# FPGA_Bank_0_CFG.net
KiCad netlist of a schematic drawn in Altium Designer
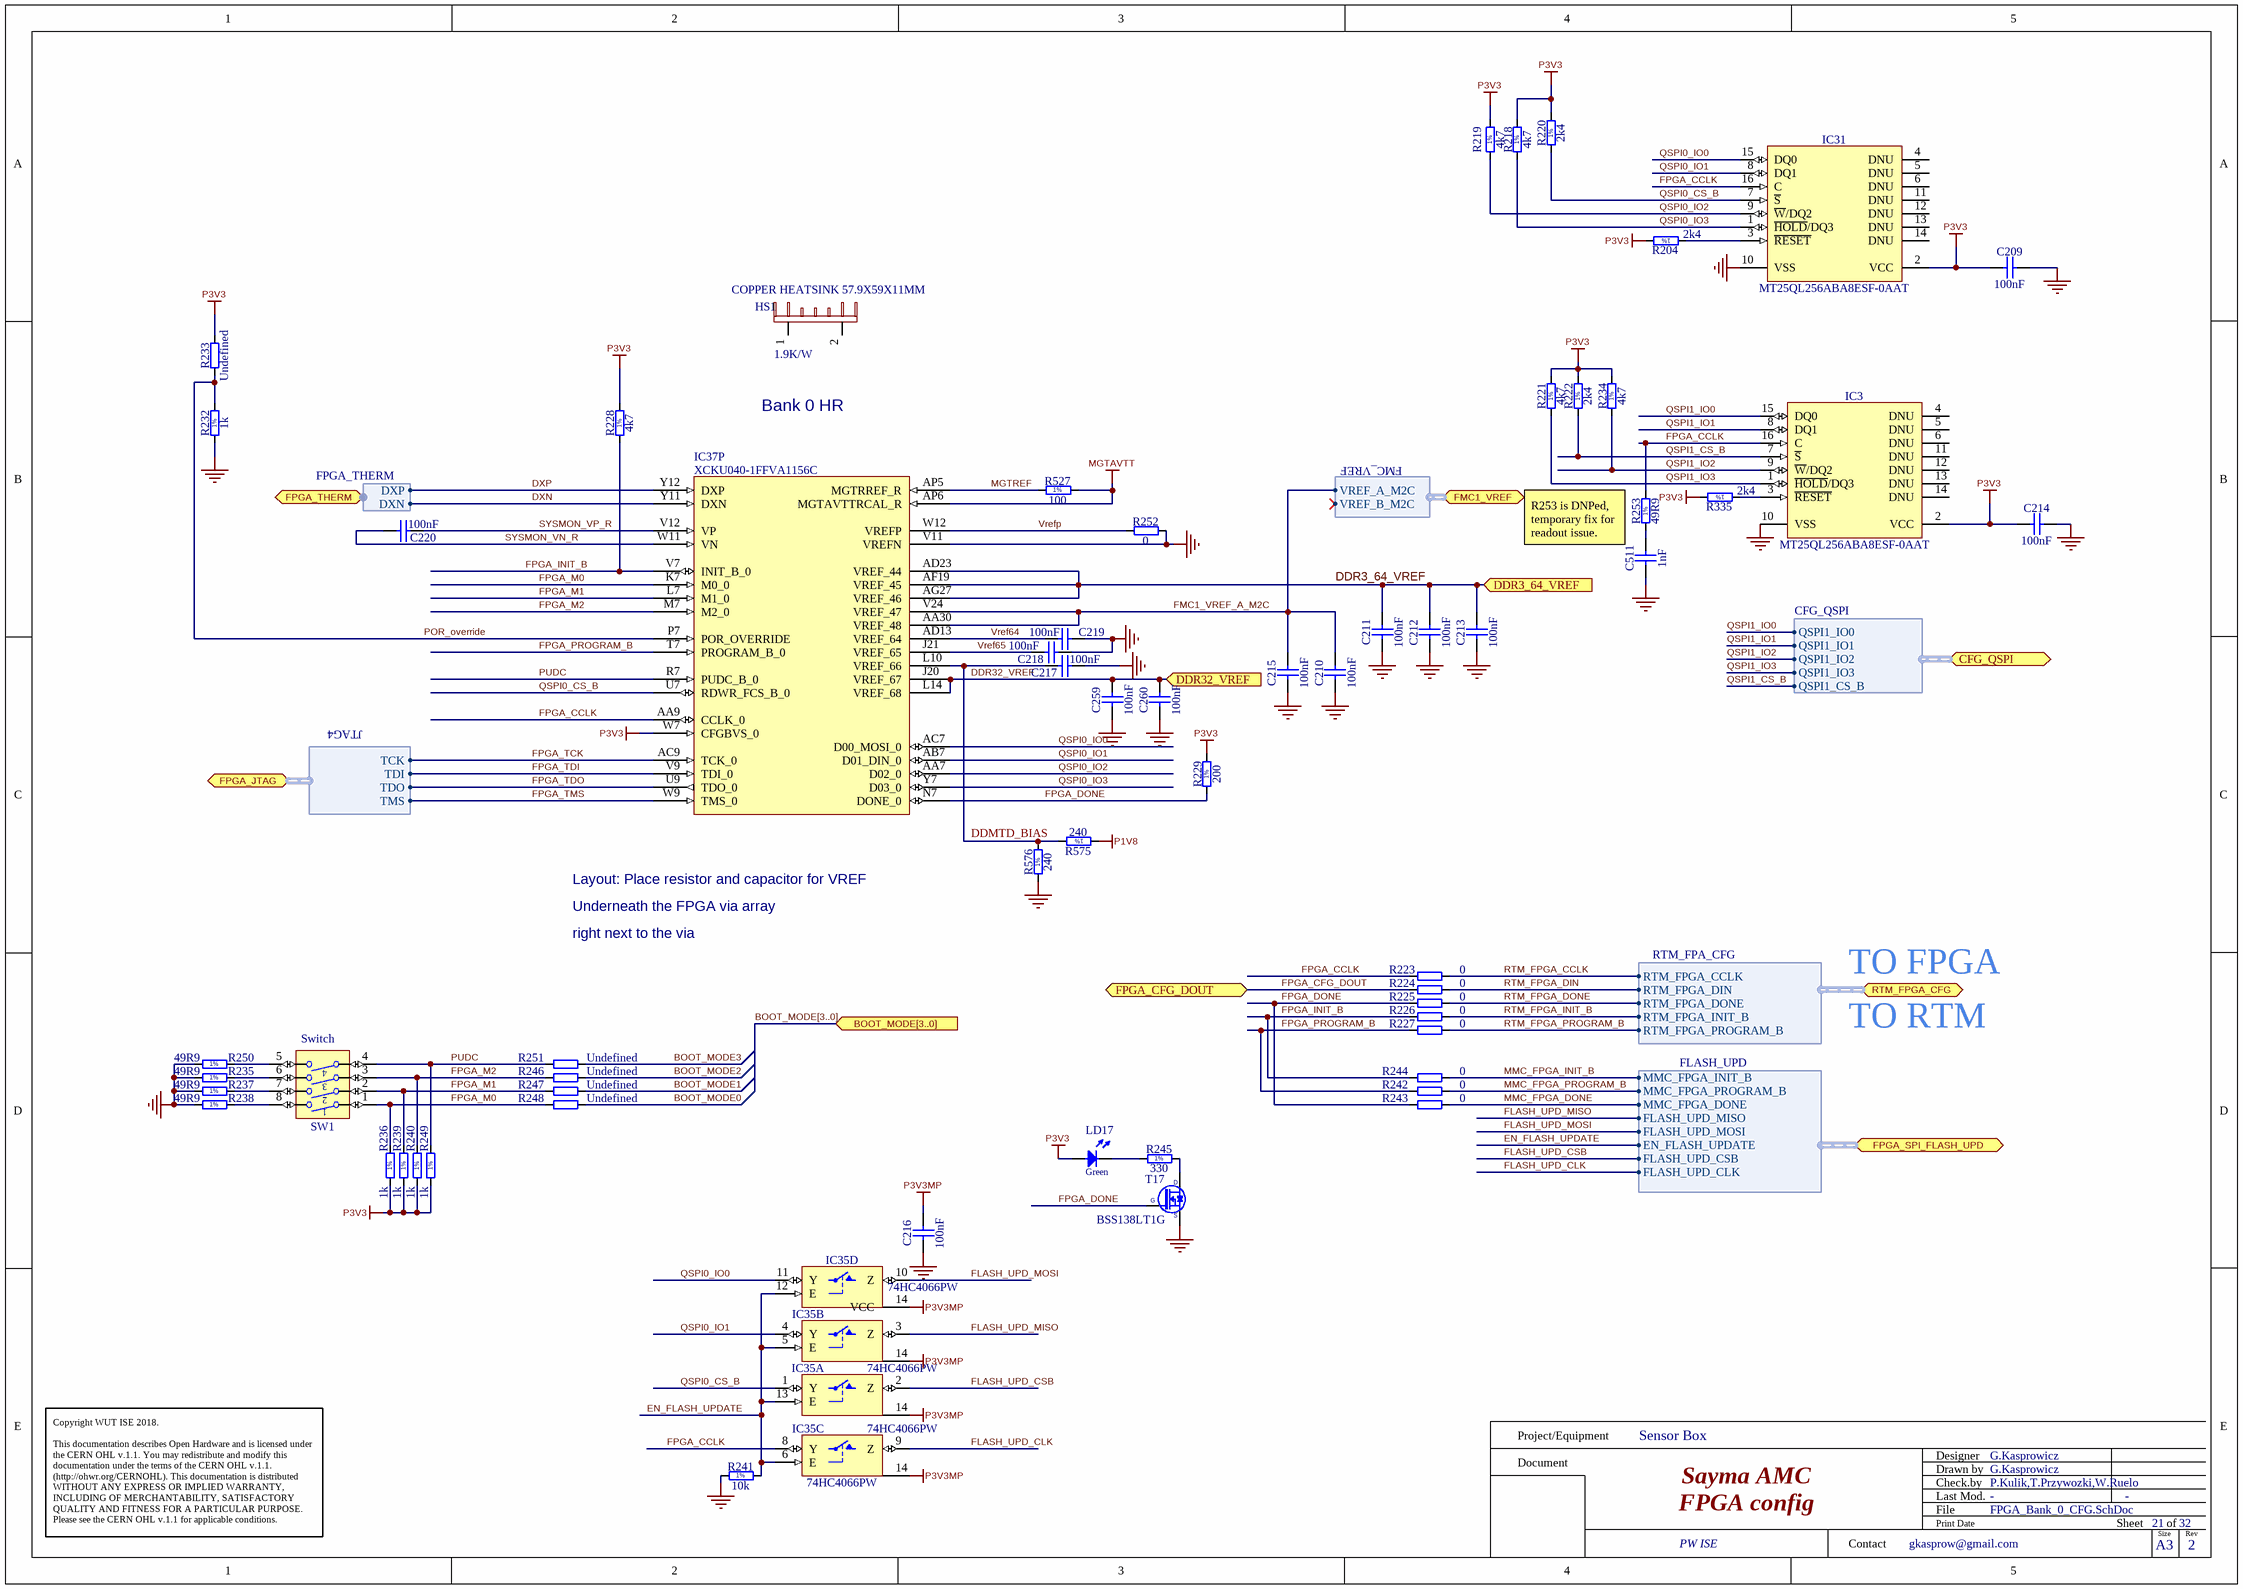
[diagram p0: FPGA_Bank_0_CFG.SchDoc]

(export (version "E")
  (design (tool "Eeschema 10.0.6"))
  (components
    (comp (ref "C209")
      (value "100nF")
      (footprint "CAPC0603X33N")
      (description "Non-polarised capacitor")
      (fields
        (field (name "MANUFACTURER PART NUMBER") "CC0201_100NF_6.3V_10%_X5R")
        (field (name "MANUFACTURER") "GENERIC")
        (field (name "AUTHOR") "CERN DEM JLC")
      )
      (libsource (lib "Capacitors") (part "Capacitor - non polarized"))
    )
    (comp (ref "C210")
      (value "100nF")
      (footprint "CAPC0603X33N")
      (description "Non-polarised capacitor")
      (fields
        (field (name "MANUFACTURER PART NUMBER") "CC0201_100NF_6.3V_10%_X5R")
        (field (name "MANUFACTURER") "GENERIC")
        (field (name "AUTHOR") "CERN DEM JLC")
      )
      (libsource (lib "Capacitors") (part "Capacitor - non polarized"))
    )
    (comp (ref "C211")
      (value "100nF")
      (footprint "CAPC0603X33N")
      (description "Non-polarised capacitor")
      (fields
        (field (name "MANUFACTURER PART NUMBER") "CC0201_100NF_6.3V_10%_X5R")
        (field (name "MANUFACTURER") "GENERIC")
        (field (name "AUTHOR") "CERN DEM JLC")
      )
      (libsource (lib "Capacitors") (part "Capacitor - non polarized"))
    )
    (comp (ref "C212")
      (value "100nF")
      (footprint "CAPC0603X33N")
      (description "Non-polarised capacitor")
      (fields
        (field (name "MANUFACTURER PART NUMBER") "CC0201_100NF_6.3V_10%_X5R")
        (field (name "MANUFACTURER") "GENERIC")
        (field (name "AUTHOR") "CERN DEM JLC")
      )
      (libsource (lib "Capacitors") (part "Capacitor - non polarized"))
    )
    (comp (ref "C213")
      (value "100nF")
      (footprint "CAPC0603X33N")
      (description "Non-polarised capacitor")
      (fields
        (field (name "MANUFACTURER PART NUMBER") "CC0201_100NF_6.3V_10%_X5R")
        (field (name "MANUFACTURER") "GENERIC")
        (field (name "AUTHOR") "CERN DEM JLC")
      )
      (libsource (lib "Capacitors") (part "Capacitor - non polarized"))
    )
    (comp (ref "C214")
      (value "100nF")
      (footprint "CAPC0603X33N")
      (description "Non-polarised capacitor")
      (fields
        (field (name "MANUFACTURER PART NUMBER") "CC0201_100NF_6.3V_10%_X5R")
        (field (name "MANUFACTURER") "GENERIC")
        (field (name "AUTHOR") "CERN DEM JLC")
      )
      (libsource (lib "Capacitors") (part "Capacitor - non polarized"))
    )
    (comp (ref "C215")
      (value "100nF")
      (footprint "CAPC0603X33N")
      (description "Non-polarised capacitor")
      (fields
        (field (name "MANUFACTURER PART NUMBER") "CC0201_100NF_6.3V_10%_X5R")
        (field (name "MANUFACTURER") "GENERIC")
        (field (name "AUTHOR") "CERN DEM JLC")
      )
      (libsource (lib "Capacitors") (part "Capacitor - non polarized"))
    )
    (comp (ref "C216")
      (value "100nF")
      (footprint "CAPC0603X33N")
      (description "Non-polarised capacitor")
      (fields
        (field (name "MANUFACTURER PART NUMBER") "CC0201_100NF_6.3V_10%_X5R")
        (field (name "MANUFACTURER") "GENERIC")
        (field (name "AUTHOR") "CERN DEM JLC")
      )
      (libsource (lib "Capacitors") (part "Capacitor - non polarized"))
    )
    (comp (ref "C217")
      (value "100nF")
      (footprint "CAPC0603X33N")
      (description "Non-polarised capacitor")
      (fields
        (field (name "MANUFACTURER PART NUMBER") "CC0201_100NF_6.3V_10%_X5R")
        (field (name "MANUFACTURER") "GENERIC")
        (field (name "AUTHOR") "CERN DEM JLC")
      )
      (libsource (lib "Capacitors") (part "Capacitor - non polarized"))
    )
    (comp (ref "C218")
      (value "100nF")
      (footprint "CAPC0603X33N")
      (description "Non-polarised capacitor")
      (fields
        (field (name "MANUFACTURER PART NUMBER") "CC0201_100NF_6.3V_10%_X5R")
        (field (name "MANUFACTURER") "GENERIC")
        (field (name "AUTHOR") "CERN DEM JLC")
      )
      (libsource (lib "Capacitors") (part "Capacitor - non polarized"))
    )
    (comp (ref "C219")
      (value "100nF")
      (footprint "CAPC0603X33N")
      (description "Non-polarised capacitor")
      (fields
        (field (name "MANUFACTURER PART NUMBER") "CC0201_100NF_6.3V_10%_X5R")
        (field (name "MANUFACTURER") "GENERIC")
        (field (name "AUTHOR") "CERN DEM JLC")
      )
      (libsource (lib "Capacitors") (part "Capacitor - non polarized"))
    )
    (comp (ref "C220")
      (value "100nF")
      (footprint "CAPC0603X33N")
      (description "Non-polarised capacitor")
      (fields
        (field (name "MANUFACTURER PART NUMBER") "CC0201_100NF_6.3V_10%_X5R")
        (field (name "MANUFACTURER") "GENERIC")
        (field (name "AUTHOR") "CERN DEM JLC")
      )
      (libsource (lib "Capacitors") (part "Capacitor - non polarized"))
    )
    (comp (ref "C259")
      (value "100nF")
      (footprint "CAPC0603X33N")
      (description "Non-polarised capacitor")
      (fields
        (field (name "MANUFACTURER PART NUMBER") "CC0201_100NF_6.3V_10%_X5R")
        (field (name "MANUFACTURER") "GENERIC")
        (field (name "AUTHOR") "CERN DEM JLC")
      )
      (libsource (lib "Capacitors") (part "Capacitor - non polarized"))
    )
    (comp (ref "C260")
      (value "100nF")
      (footprint "CAPC0603X33N")
      (description "Non-polarised capacitor")
      (fields
        (field (name "MANUFACTURER PART NUMBER") "CC0201_100NF_6.3V_10%_X5R")
        (field (name "MANUFACTURER") "GENERIC")
        (field (name "AUTHOR") "CERN DEM JLC")
      )
      (libsource (lib "Capacitors") (part "Capacitor - non polarized"))
    )
    (comp (ref "C511")
      (value "1nF")
      (footprint "CAPC1005X55N")
      (description "Non-polarised capacitor")
      (fields
        (field (name "MANUFACTURER PART NUMBER") "CC0402_1NF_50V_10%_X7R")
        (field (name "MANUFACTURER") "GENERIC")
        (field (name "AUTHOR") "CERN DEM JLC")
      )
      (libsource (lib "Capacitors") (part "Capacitor - non polarized"))
    )
    (comp (ref "HS1")
      (value "1.9K/W")
      (footprint "HS_AAVID_342947")
      (fields
        (field (name "MANUFACTURER PART NUMBER") "342947")
        (field (name "MANUFACTURER") "Aavid Thermalloy")
        (field (name "PART DESCRIPTION") "COPPER HEATSINK 57.9X59X11MM")
        (field (name "PART NUMBER") "HSINK_AAVID_342947")
      )
      (libsource (lib "altium-import") (part "root_0__*"))
    )
    (comp (ref "IC3")
      (value "MT25QL256ABA8ESF-0AAT")
      (footprint "SOIC127P1030X265-16N")
      (description "256Mbit (32MB), 2.7V-3.6V, Multiple I/O Serial NOR Flash Memory,with Reset# & Hold#")
      (fields (field (name "MANUFACTURER") "MICRON TECHNOLOGY") (field (name "AUTHOR") "CERN DEM JLC"))
      (libsource (lib "ICs And Semiconductors") (part "MT25QL256ABA8ESF"))
    )
    (comp (ref "IC31")
      (value "MT25QL256ABA8ESF-0AAT")
      (footprint "SOIC127P1030X265-16N")
      (description "256Mbit (32MB), 2.7V-3.6V, Multiple I/O Serial NOR Flash Memory,with Reset# & Hold#")
      (fields (field (name "MANUFACTURER") "MICRON TECHNOLOGY") (field (name "AUTHOR") "CERN DEM JLC"))
      (libsource (lib "ICs And Semiconductors") (part "MT25QL256ABA8ESF"))
    )
    (comp (ref "IC35")
      (value "74HC4066PW")
      (footprint "SOP65P640X110-14N")
      (fields (field (name "MANUFACTURER") "NXP SEMICONDUCTORS") (field (name "AUTHOR") "CERN DEM JLC"))
      (libsource (lib "ICs And Semiconductors") (part "4066"))
    )
    (comp (ref "IC37")
      (value "XCKU040-1FFVA1156C")
      (footprint "BGA1156C100P34X34_3500X3500X350")
      (description "Kintex UltraScale FPGA, 520 I/O, 530K Cells, 1156-Ball BGA, Speed Grade 1, Commercial Grade")
      (fields (field (name "MANUFACTURER") "XILINX") (field (name "AUTHOR") "CERN DEM CA"))
      (libsource (lib "ICs And Semiconductors") (part "XCKU040-1FFVA1156C"))
    )
    (comp (ref "LD17")
      (value "Green")
      (footprint "LED_AVAGO_HSME-C120")
      (description "LED Green 1C 2A")
      (fields
        (field (name "MANUFACTURER PART NUMBER") "HSME-C120")
        (field (name "MANUFACTURER") "AVAGO TECHNOLOGIES")
        (field (name "AUTHOR") "CERN DEM JMW")
      )
      (libsource (lib "ICs And Semiconductors") (part "LED Green 1C 2A"))
    )
    (comp (ref "R204")
      (value "2k4")
      (footprint "RESC1005X40N")
      (description "Resistor - 1%")
      (fields
        (field (name "MANUFACTURER PART NUMBER") "R0402_2K4_1%_0.0625W_100PPM")
        (field (name "MANUFACTURER") "GENERIC")
        (field (name "AUTHOR") "CERN DEM JLC")
      )
      (libsource (lib "Resistors") (part "Resistor - 1%"))
    )
    (comp (ref "R218")
      (value "4k7")
      (footprint "RESC1005X40N")
      (description "Resistor - 1%")
      (fields
        (field (name "MANUFACTURER PART NUMBER") "R0402_4K7_1%_0.0625W_100PPM")
        (field (name "MANUFACTURER") "GENERIC")
        (field (name "AUTHOR") "CERN DEM JLC")
      )
      (libsource (lib "Resistors") (part "Resistor - 1%"))
    )
    (comp (ref "R219")
      (value "4k7")
      (footprint "RESC1005X40N")
      (description "Resistor - 1%")
      (fields
        (field (name "MANUFACTURER PART NUMBER") "R0402_4K7_1%_0.0625W_100PPM")
        (field (name "MANUFACTURER") "GENERIC")
        (field (name "AUTHOR") "CERN DEM JLC")
      )
      (libsource (lib "Resistors") (part "Resistor - 1%"))
    )
    (comp (ref "R220")
      (value "2k4")
      (footprint "RESC1005X40N")
      (description "Resistor - 1%")
      (fields
        (field (name "MANUFACTURER PART NUMBER") "R0402_2K4_1%_0.0625W_100PPM")
        (field (name "MANUFACTURER") "GENERIC")
        (field (name "AUTHOR") "CERN DEM JLC")
      )
      (libsource (lib "Resistors") (part "Resistor - 1%"))
    )
    (comp (ref "R221")
      (value "4k7")
      (footprint "RESC1005X40N")
      (description "Resistor - 1%")
      (fields
        (field (name "MANUFACTURER PART NUMBER") "R0402_4K7_1%_0.0625W_100PPM")
        (field (name "MANUFACTURER") "GENERIC")
        (field (name "AUTHOR") "CERN DEM JLC")
      )
      (libsource (lib "Resistors") (part "Resistor - 1%"))
    )
    (comp (ref "R222")
      (value "2k4")
      (footprint "RESC1005X40N")
      (description "Resistor - 1%")
      (fields
        (field (name "MANUFACTURER PART NUMBER") "R0402_2K4_1%_0.0625W_100PPM")
        (field (name "MANUFACTURER") "GENERIC")
        (field (name "AUTHOR") "CERN DEM JLC")
      )
      (libsource (lib "Resistors") (part "Resistor - 1%"))
    )
    (comp (ref "R223")
      (value "0")
      (footprint "RESC1005X40N")
      (description "Resistor")
      (fields
        (field (name "MANUFACTURER PART NUMBER") "R0402_0R_JUMPER")
        (field (name "MANUFACTURER") "GENERIC")
        (field (name "AUTHOR") "CERN DEM JLC")
      )
      (libsource (lib "Resistors") (part "Resistor"))
    )
    (comp (ref "R224")
      (value "0")
      (footprint "RESC1005X40N")
      (description "Resistor")
      (fields
        (field (name "MANUFACTURER PART NUMBER") "R0402_0R_JUMPER")
        (field (name "MANUFACTURER") "GENERIC")
        (field (name "AUTHOR") "CERN DEM JLC")
      )
      (libsource (lib "Resistors") (part "Resistor"))
    )
    (comp (ref "R225")
      (value "0")
      (footprint "RESC1005X40N")
      (description "Resistor")
      (fields
        (field (name "MANUFACTURER PART NUMBER") "R0402_0R_JUMPER")
        (field (name "MANUFACTURER") "GENERIC")
        (field (name "AUTHOR") "CERN DEM JLC")
      )
      (libsource (lib "Resistors") (part "Resistor"))
    )
    (comp (ref "R226")
      (value "0")
      (footprint "RESC1005X40N")
      (description "Resistor")
      (fields
        (field (name "MANUFACTURER PART NUMBER") "R0402_0R_JUMPER")
        (field (name "MANUFACTURER") "GENERIC")
        (field (name "AUTHOR") "CERN DEM JLC")
      )
      (libsource (lib "Resistors") (part "Resistor"))
    )
    (comp (ref "R227")
      (value "0")
      (footprint "RESC1005X40N")
      (description "Resistor")
      (fields
        (field (name "MANUFACTURER PART NUMBER") "R0402_0R_JUMPER")
        (field (name "MANUFACTURER") "GENERIC")
        (field (name "AUTHOR") "CERN DEM JLC")
      )
      (libsource (lib "Resistors") (part "Resistor"))
    )
    (comp (ref "R228")
      (value "4k7")
      (footprint "RESC1005X40N")
      (description "Resistor - 1%")
      (fields
        (field (name "MANUFACTURER PART NUMBER") "R0402_4K7_1%_0.0625W_100PPM")
        (field (name "MANUFACTURER") "GENERIC")
        (field (name "AUTHOR") "CERN DEM JLC")
      )
      (libsource (lib "Resistors") (part "Resistor - 1%"))
    )
    (comp (ref "R229")
      (value "200")
      (footprint "RESC1005X40N")
      (description "Resistor - 1%")
      (fields
        (field (name "MANUFACTURER PART NUMBER") "R0402_200R_1%_0.0625W_100PPM")
        (field (name "MANUFACTURER") "GENERIC")
        (field (name "AUTHOR") "CERN DEM JLC")
      )
      (libsource (lib "Resistors") (part "Resistor - 1%"))
    )
    (comp (ref "R232")
      (value "1k")
      (footprint "RESC1005X40N")
      (description "Resistor - 1%")
      (fields
        (field (name "MANUFACTURER PART NUMBER") "R0402_1K_1%_0.0625W_100PPM")
        (field (name "MANUFACTURER") "GENERIC")
        (field (name "AUTHOR") "CERN DEM JLC")
      )
      (libsource (lib "Resistors") (part "Resistor - 1%"))
    )
    (comp (ref "R233")
      (value "Undefined")
      (footprint "RESC1005X40N")
      (description "Resistor")
      (fields
        (field (name "MANUFACTURER PART NUMBER") "R0402_NO-VALUE")
        (field (name "AUTHOR") "CERN DEM JLC")
      )
      (libsource (lib "Resistors") (part "Resistor"))
    )
    (comp (ref "R234")
      (value "4k7")
      (footprint "RESC1005X40N")
      (description "Resistor - 1%")
      (fields
        (field (name "MANUFACTURER PART NUMBER") "R0402_4K7_1%_0.0625W_100PPM")
        (field (name "MANUFACTURER") "GENERIC")
        (field (name "AUTHOR") "CERN DEM JLC")
      )
      (libsource (lib "Resistors") (part "Resistor - 1%"))
    )
    (comp (ref "R235")
      (value "49R9")
      (footprint "RESC1005X40N")
      (description "Resistor - 1%")
      (fields
        (field (name "MANUFACTURER PART NUMBER") "R0402_49R9_1%_0.0625W_100PPM")
        (field (name "MANUFACTURER") "GENERIC")
        (field (name "AUTHOR") "CERN DEM JLC")
      )
      (libsource (lib "Resistors") (part "Resistor - 1%"))
    )
    (comp (ref "R236")
      (value "1k")
      (footprint "RESC1005X40N")
      (description "Resistor - 1%")
      (fields
        (field (name "MANUFACTURER PART NUMBER") "R0402_1K_1%_0.0625W_100PPM")
        (field (name "MANUFACTURER") "GENERIC")
        (field (name "AUTHOR") "CERN DEM JLC")
      )
      (libsource (lib "Resistors") (part "Resistor - 1%"))
    )
    (comp (ref "R237")
      (value "49R9")
      (footprint "RESC1005X40N")
      (description "Resistor - 1%")
      (fields
        (field (name "MANUFACTURER PART NUMBER") "R0402_49R9_1%_0.0625W_100PPM")
        (field (name "MANUFACTURER") "GENERIC")
        (field (name "AUTHOR") "CERN DEM JLC")
      )
      (libsource (lib "Resistors") (part "Resistor - 1%"))
    )
    (comp (ref "R238")
      (value "49R9")
      (footprint "RESC1005X40N")
      (description "Resistor - 1%")
      (fields
        (field (name "MANUFACTURER PART NUMBER") "R0402_49R9_1%_0.0625W_100PPM")
        (field (name "MANUFACTURER") "GENERIC")
        (field (name "AUTHOR") "CERN DEM JLC")
      )
      (libsource (lib "Resistors") (part "Resistor - 1%"))
    )
    (comp (ref "R239")
      (value "1k")
      (footprint "RESC1005X40N")
      (description "Resistor - 1%")
      (fields
        (field (name "MANUFACTURER PART NUMBER") "R0402_1K_1%_0.0625W_100PPM")
        (field (name "MANUFACTURER") "GENERIC")
        (field (name "AUTHOR") "CERN DEM JLC")
      )
      (libsource (lib "Resistors") (part "Resistor - 1%"))
    )
    (comp (ref "R240")
      (value "1k")
      (footprint "RESC1005X40N")
      (description "Resistor - 1%")
      (fields
        (field (name "MANUFACTURER PART NUMBER") "R0402_1K_1%_0.0625W_100PPM")
        (field (name "MANUFACTURER") "GENERIC")
        (field (name "AUTHOR") "CERN DEM JLC")
      )
      (libsource (lib "Resistors") (part "Resistor - 1%"))
    )
    (comp (ref "R241")
      (value "10k")
      (footprint "RESC1005X40N")
      (description "Resistor - 1%")
      (fields
        (field (name "MANUFACTURER PART NUMBER") "R0402_10K_1%_0.0625W_100PPM")
        (field (name "MANUFACTURER") "GENERIC")
        (field (name "AUTHOR") "CERN DEM JLC")
      )
      (libsource (lib "Resistors") (part "Resistor - 1%"))
    )
    (comp (ref "R242")
      (value "0")
      (footprint "RESC1005X40N")
      (description "Resistor")
      (fields
        (field (name "MANUFACTURER PART NUMBER") "R0402_0R_JUMPER")
        (field (name "MANUFACTURER") "GENERIC")
        (field (name "AUTHOR") "CERN DEM JLC")
      )
      (libsource (lib "Resistors") (part "Resistor"))
    )
    (comp (ref "R243")
      (value "0")
      (footprint "RESC1005X40N")
      (description "Resistor")
      (fields
        (field (name "MANUFACTURER PART NUMBER") "R0402_0R_JUMPER")
        (field (name "MANUFACTURER") "GENERIC")
        (field (name "AUTHOR") "CERN DEM JLC")
      )
      (libsource (lib "Resistors") (part "Resistor"))
    )
    (comp (ref "R244")
      (value "0")
      (footprint "RESC1005X40N")
      (description "Resistor")
      (fields
        (field (name "MANUFACTURER PART NUMBER") "R0402_0R_JUMPER")
        (field (name "MANUFACTURER") "GENERIC")
        (field (name "AUTHOR") "CERN DEM JLC")
      )
      (libsource (lib "Resistors") (part "Resistor"))
    )
    (comp (ref "R245")
      (value "330")
      (footprint "RESC1005X40N")
      (description "Resistor - 1%")
      (fields
        (field (name "MANUFACTURER PART NUMBER") "R0402_330R_1%_0.0625W_100PPM")
        (field (name "MANUFACTURER") "GENERIC")
        (field (name "AUTHOR") "CERN DEM JLC")
      )
      (libsource (lib "Resistors") (part "Resistor - 1%"))
    )
    (comp (ref "R246")
      (value "Undefined")
      (footprint "RESC1005X40N")
      (description "Resistor")
      (fields
        (field (name "MANUFACTURER PART NUMBER") "R0402_NO-VALUE")
        (field (name "AUTHOR") "CERN DEM JLC")
      )
      (libsource (lib "Resistors") (part "Resistor"))
    )
    (comp (ref "R247")
      (value "Undefined")
      (footprint "RESC1005X40N")
      (description "Resistor")
      (fields
        (field (name "MANUFACTURER PART NUMBER") "R0402_NO-VALUE")
        (field (name "AUTHOR") "CERN DEM JLC")
      )
      (libsource (lib "Resistors") (part "Resistor"))
    )
    (comp (ref "R248")
      (value "Undefined")
      (footprint "RESC1005X40N")
      (description "Resistor")
      (fields
        (field (name "MANUFACTURER PART NUMBER") "R0402_NO-VALUE")
        (field (name "AUTHOR") "CERN DEM JLC")
      )
      (libsource (lib "Resistors") (part "Resistor"))
    )
    (comp (ref "R249")
      (value "1k")
      (footprint "RESC1005X40N")
      (description "Resistor - 1%")
      (fields
        (field (name "MANUFACTURER PART NUMBER") "R0402_1K_1%_0.0625W_100PPM")
        (field (name "MANUFACTURER") "GENERIC")
        (field (name "AUTHOR") "CERN DEM JLC")
      )
      (libsource (lib "Resistors") (part "Resistor - 1%"))
    )
    (comp (ref "R250")
      (value "49R9")
      (footprint "RESC1005X40N")
      (description "Resistor - 1%")
      (fields
        (field (name "MANUFACTURER PART NUMBER") "R0402_49R9_1%_0.0625W_100PPM")
        (field (name "MANUFACTURER") "GENERIC")
        (field (name "AUTHOR") "CERN DEM JLC")
      )
      (libsource (lib "Resistors") (part "Resistor - 1%"))
    )
    (comp (ref "R251")
      (value "Undefined")
      (footprint "RESC1005X40N")
      (description "Resistor")
      (fields
        (field (name "MANUFACTURER PART NUMBER") "R0402_NO-VALUE")
        (field (name "AUTHOR") "CERN DEM JLC")
      )
      (libsource (lib "Resistors") (part "Resistor"))
    )
    (comp (ref "R252")
      (value "0")
      (footprint "RESC1005X40N")
      (description "Resistor")
      (fields
        (field (name "MANUFACTURER PART NUMBER") "R0402_0R_JUMPER")
        (field (name "MANUFACTURER") "GENERIC")
        (field (name "AUTHOR") "CERN DEM JLC")
      )
      (libsource (lib "Resistors") (part "Resistor"))
    )
    (comp (ref "R253")
      (value "49R9")
      (footprint "RESC1005X40N")
      (description "Resistor - 1%")
      (fields
        (field (name "MANUFACTURER PART NUMBER") "R0402_49R9_1%_0.0625W_100PPM")
        (field (name "MANUFACTURER") "GENERIC")
        (field (name "AUTHOR") "CERN DEM JLC")
      )
      (libsource (lib "Resistors") (part "Resistor - 1%"))
    )
    (comp (ref "R335")
      (value "2k4")
      (footprint "RESC1005X40N")
      (description "Resistor - 1%")
      (fields
        (field (name "MANUFACTURER PART NUMBER") "R0402_2K4_1%_0.0625W_100PPM")
        (field (name "MANUFACTURER") "GENERIC")
        (field (name "AUTHOR") "CERN DEM JLC")
      )
      (libsource (lib "Resistors") (part "Resistor - 1%"))
    )
    (comp (ref "R527")
      (value "100")
      (footprint "RESC0603X28N")
      (description "Resistor - 1%")
      (fields
        (field (name "MANUFACTURER PART NUMBER") "R0201_100R_1%_0.05W_200PPM")
        (field (name "MANUFACTURER") "GENERIC")
        (field (name "AUTHOR") "CERN DEM JLC")
      )
      (libsource (lib "Resistors") (part "Resistor - 1%"))
    )
    (comp (ref "R575")
      (value "240")
      (footprint "RESC1005X40N")
      (description "Resistor - 1%")
      (fields
        (field (name "MANUFACTURER PART NUMBER") "R0402_240R_1%_0.0625W_100PPM")
        (field (name "MANUFACTURER") "GENERIC")
        (field (name "AUTHOR") "CERN DEM JLC")
      )
      (libsource (lib "Resistors") (part "Resistor - 1%"))
    )
    (comp (ref "R576")
      (value "240")
      (footprint "RESC1005X40N")
      (description "Resistor - 1%")
      (fields
        (field (name "MANUFACTURER PART NUMBER") "R0402_240R_1%_0.0625W_100PPM")
        (field (name "MANUFACTURER") "GENERIC")
        (field (name "AUTHOR") "CERN DEM JLC")
      )
      (libsource (lib "Resistors") (part "Resistor - 1%"))
    )
    (comp (ref "SW1")
      (value "Switch")
      (footprint "SW_TYCO_1571983-4")
      (description "4 Ways SPST DIP Switch")
      (fields
        (field (name "MANUFACTURER PART NUMBER") "1571983-4 or GDH04S04")
        (field (name "MANUFACTURER") "TYCO")
        (field (name "AUTHOR") "CERN DEM JLC")
      )
      (libsource (lib "Eletro-mechanical") (part "SW 4x SPST DIP Switch"))
    )
    (comp (ref "T17")
      (value "BSS138LT1G")
      (footprint "SOT95P240X110-3N")
      (description "N-CHANNEL MOSFET WITH DIODE")
      (fields (field (name "MANUFACTURER") "ON SEMICONDUCTOR") (field (name "AUTHOR") "CERN DEM JLC"))
      (libsource (lib "ICs And Semiconductors") (part "N-MOSFET-D 1G 2S 3D"))
    )
  )
  (nets
    (net (code "7") (name "/BOOT_MODE0") (class "Default")
      (node (ref "R248") (pin "2") (pinfunction "2_2") (pintype "passive"))
    )
    (net (code "8") (name "/BOOT_MODE1") (class "Default")
      (node (ref "R247") (pin "2") (pinfunction "2_2") (pintype "passive"))
    )
    (net (code "9") (name "/BOOT_MODE2") (class "Default")
      (node (ref "R246") (pin "2") (pinfunction "2_2") (pintype "passive"))
    )
    (net (code "10") (name "/BOOT_MODE3") (class "Default")
      (node (ref "R251") (pin "2") (pinfunction "2_2") (pintype "passive"))
    )
    (net (code "12") (name "/DDMTD_BIAS") (class "Default")
      (node (ref "C217") (pin "1") (pinfunction "1_1") (pintype "passive"))
      (node (ref "IC37") (pin "L10") (pinfunction "VREF_66_L10") (pintype "power_in"))
      (node (ref "R575") (pin "2") (pinfunction "2_2") (pintype "passive"))
      (node (ref "R576") (pin "2") (pinfunction "2_2") (pintype "passive"))
    )
    (net (code "13") (name "/DDR3_64_VREF") (class "Default")
      (node (ref "C211") (pin "1") (pinfunction "1_1") (pintype "passive"))
      (node (ref "C212") (pin "1") (pinfunction "1_1") (pintype "passive"))
      (node (ref "C213") (pin "1") (pinfunction "1_1") (pintype "passive"))
      (node (ref "IC37") (pin "AD23") (pinfunction "VREF_44_AD23") (pintype "power_in"))
      (node (ref "IC37") (pin "AF19") (pinfunction "VREF_45_AF19") (pintype "power_in"))
      (node (ref "IC37") (pin "AG27") (pinfunction "VREF_46_AG27") (pintype "power_in"))
    )
    (net (code "14") (name "/DDR32_VREF") (class "Default")
      (node (ref "C259") (pin "1") (pinfunction "1_1") (pintype "passive"))
      (node (ref "C260") (pin "1") (pinfunction "1_1") (pintype "passive"))
      (node (ref "IC37") (pin "J20") (pinfunction "VREF_67_J20") (pintype "power_in"))
      (node (ref "IC37") (pin "L14") (pinfunction "VREF_68_L14") (pintype "power_in"))
    )
    (net (code "15") (name "/DXN") (class "Default")
      (node (ref "IC37") (pin "Y11") (pinfunction "DXN_Y11") (pintype "input"))
    )
    (net (code "16") (name "/DXP") (class "Default")
      (node (ref "IC37") (pin "Y12") (pinfunction "DXP_Y12") (pintype "input"))
    )
    (net (code "17") (name "/EN_FLASH_UPDATE") (class "Default")
      (node (ref "IC35") (pin "12") (pinfunction "E_12") (pintype "input"))
      (node (ref "IC35") (pin "13") (pinfunction "E_13") (pintype "input"))
      (node (ref "IC35") (pin "5") (pinfunction "E_5") (pintype "input"))
      (node (ref "IC35") (pin "6") (pinfunction "E_6") (pintype "input"))
      (node (ref "R241") (pin "2") (pinfunction "2_2") (pintype "passive"))
    )
    (net (code "18") (name "/FLASH_UPD_CLK") (class "Default")
      (node (ref "IC35") (pin "9") (pinfunction "Z_9") (pintype "bidirectional"))
    )
    (net (code "19") (name "/FLASH_UPD_CSB") (class "Default")
      (node (ref "IC35") (pin "2") (pinfunction "Z_2") (pintype "bidirectional"))
    )
    (net (code "20") (name "/FLASH_UPD_MISO") (class "Default")
      (node (ref "IC35") (pin "3") (pinfunction "Z_3") (pintype "bidirectional"))
    )
    (net (code "21") (name "/FLASH_UPD_MOSI") (class "Default")
      (node (ref "IC35") (pin "10") (pinfunction "Z_10") (pintype "bidirectional"))
    )
    (net (code "22") (name "/FMC1_VREF_A_M2C") (class "Default")
      (node (ref "C210") (pin "1") (pinfunction "1_1") (pintype "passive"))
      (node (ref "C215") (pin "1") (pinfunction "1_1") (pintype "passive"))
      (node (ref "IC37") (pin "AA30") (pinfunction "VREF_48_AA30") (pintype "power_in"))
      (node (ref "IC37") (pin "V24") (pinfunction "VREF_47_V24") (pintype "power_in"))
    )
    (net (code "23") (name "/FPGA_CCLK") (class "Default")
      (node (ref "IC3") (pin "16") (pinfunction "C_16") (pintype "input"))
      (node (ref "IC31") (pin "16") (pinfunction "C_16") (pintype "input"))
      (node (ref "IC35") (pin "8") (pinfunction "Y_8") (pintype "bidirectional"))
      (node (ref "IC37") (pin "AA9") (pinfunction "CCLK_0_AA9") (pintype "bidirectional"))
      (node (ref "R223") (pin "1") (pinfunction "1_1") (pintype "passive"))
      (node (ref "R253") (pin "2") (pinfunction "2_2") (pintype "passive"))
    )
    (net (code "24") (name "/FPGA_CFG_DOUT") (class "Default")
      (node (ref "R224") (pin "1") (pinfunction "1_1") (pintype "passive"))
    )
    (net (code "25") (name "/FPGA_DONE") (class "Default")
      (node (ref "IC37") (pin "N7") (pinfunction "DONE_0_N7") (pintype "bidirectional"))
      (node (ref "R225") (pin "1") (pinfunction "1_1") (pintype "passive"))
      (node (ref "R229") (pin "1") (pinfunction "1_1") (pintype "passive"))
      (node (ref "R243") (pin "1") (pinfunction "1_1") (pintype "passive"))
      (node (ref "T17") (pin "1") (pinfunction "G_1") (pintype "passive"))
    )
    (net (code "26") (name "/FPGA_INIT_B") (class "Default")
      (node (ref "IC37") (pin "V7") (pinfunction "INIT_B_0_V7") (pintype "bidirectional"))
      (node (ref "R226") (pin "1") (pinfunction "1_1") (pintype "passive"))
      (node (ref "R228") (pin "1") (pinfunction "1_1") (pintype "passive"))
      (node (ref "R244") (pin "1") (pinfunction "1_1") (pintype "passive"))
    )
    (net (code "27") (name "/FPGA_M0") (class "Default")
      (node (ref "IC37") (pin "K7") (pinfunction "M0_0_K7") (pintype "input"))
      (node (ref "R236") (pin "2") (pinfunction "2_2") (pintype "passive"))
      (node (ref "R248") (pin "1") (pinfunction "1_1") (pintype "passive"))
      (node (ref "SW1") (pin "1") (pinfunction "1_1") (pintype "bidirectional"))
    )
    (net (code "28") (name "/FPGA_M1") (class "Default")
      (node (ref "IC37") (pin "L7") (pinfunction "M1_0_L7") (pintype "input"))
      (node (ref "R239") (pin "2") (pinfunction "2_2") (pintype "passive"))
      (node (ref "R247") (pin "1") (pinfunction "1_1") (pintype "passive"))
      (node (ref "SW1") (pin "2") (pinfunction "2_2") (pintype "bidirectional"))
    )
    (net (code "29") (name "/FPGA_M2") (class "Default")
      (node (ref "IC37") (pin "M7") (pinfunction "M2_0_M7") (pintype "input"))
      (node (ref "R240") (pin "2") (pinfunction "2_2") (pintype "passive"))
      (node (ref "R246") (pin "1") (pinfunction "1_1") (pintype "passive"))
      (node (ref "SW1") (pin "3") (pinfunction "3_3") (pintype "bidirectional"))
    )
    (net (code "30") (name "/FPGA_PROGRAM_B") (class "Default")
      (node (ref "IC37") (pin "T7") (pinfunction "PROGRAM_B_0_T7") (pintype "input"))
      (node (ref "R227") (pin "1") (pinfunction "1_1") (pintype "passive"))
      (node (ref "R242") (pin "1") (pinfunction "1_1") (pintype "passive"))
    )
    (net (code "31") (name "/FPGA_TCK") (class "Default")
      (node (ref "IC37") (pin "AC9") (pinfunction "TCK_0_AC9") (pintype "input"))
    )
    (net (code "32") (name "/FPGA_TDI") (class "Default")
      (node (ref "IC37") (pin "V9") (pinfunction "TDI_0_V9") (pintype "input"))
    )
    (net (code "33") (name "/FPGA_TDO") (class "Default")
      (node (ref "IC37") (pin "U9") (pinfunction "TDO_0_U9") (pintype "output"))
    )
    (net (code "34") (name "/FPGA_TMS") (class "Default")
      (node (ref "IC37") (pin "W9") (pinfunction "TMS_0_W9") (pintype "input"))
    )
    (net (code "35") (name "/MGTREF") (class "Default")
      (node (ref "IC37") (pin "AP5") (pinfunction "MGTRREF_R_AP5") (pintype "input"))
      (node (ref "R527") (pin "1") (pinfunction "1_1") (pintype "passive"))
    )
    (net (code "36") (name "/MMC_FPGA_DONE") (class "Default")
      (node (ref "R243") (pin "2") (pinfunction "2_2") (pintype "passive"))
    )
    (net (code "37") (name "/MMC_FPGA_INIT_B") (class "Default")
      (node (ref "R244") (pin "2") (pinfunction "2_2") (pintype "passive"))
    )
    (net (code "38") (name "/MMC_FPGA_PROGRAM_B") (class "Default")
      (node (ref "R242") (pin "2") (pinfunction "2_2") (pintype "passive"))
    )
    (net (code "39") (name "/POR_override") (class "Default")
      (node (ref "IC37") (pin "P7") (pinfunction "POR_OVERRIDE_P7") (pintype "input"))
      (node (ref "R232") (pin "2") (pinfunction "2_2") (pintype "passive"))
      (node (ref "R233") (pin "1") (pinfunction "1_1") (pintype "passive"))
    )
    (net (code "40") (name "/PUDC") (class "Default")
      (node (ref "IC37") (pin "R7") (pinfunction "PUDC_B_0_R7") (pintype "input"))
      (node (ref "R249") (pin "2") (pinfunction "2_2") (pintype "passive"))
      (node (ref "R251") (pin "1") (pinfunction "1_1") (pintype "passive"))
      (node (ref "SW1") (pin "4") (pinfunction "4_4") (pintype "bidirectional"))
    )
    (net (code "41") (name "/QSPI0_CS_B") (class "Default")
      (node (ref "IC31") (pin "7") (pinfunction "~{S}_7") (pintype "input"))
      (node (ref "IC35") (pin "1") (pinfunction "Y_1") (pintype "bidirectional"))
      (node (ref "IC37") (pin "U7") (pinfunction "RDWR_FCS_B_0_U7") (pintype "bidirectional"))
      (node (ref "R220") (pin "1") (pinfunction "1_1") (pintype "passive"))
    )
    (net (code "42") (name "/QSPI0_IO0") (class "Default")
      (node (ref "IC31") (pin "15") (pinfunction "DQ0_15") (pintype "bidirectional"))
      (node (ref "IC35") (pin "11") (pinfunction "Y_11") (pintype "bidirectional"))
      (node (ref "IC37") (pin "AC7") (pinfunction "D00_MOSI_0_AC7") (pintype "bidirectional"))
    )
    (net (code "43") (name "/QSPI0_IO1") (class "Default")
      (node (ref "IC31") (pin "8") (pinfunction "DQ1_8") (pintype "bidirectional"))
      (node (ref "IC35") (pin "4") (pinfunction "Y_4") (pintype "bidirectional"))
      (node (ref "IC37") (pin "AB7") (pinfunction "D01_DIN_0_AB7") (pintype "bidirectional"))
    )
    (net (code "44") (name "/QSPI0_IO2") (class "Default")
      (node (ref "IC31") (pin "9") (pinfunction "~{W}/DQ2_9") (pintype "bidirectional"))
      (node (ref "IC37") (pin "AA7") (pinfunction "D02_0_AA7") (pintype "bidirectional"))
      (node (ref "R219") (pin "1") (pinfunction "1_1") (pintype "passive"))
    )
    (net (code "45") (name "/QSPI0_IO3") (class "Default")
      (node (ref "IC31") (pin "1") (pinfunction "~{HOLD}/DQ3_1") (pintype "bidirectional"))
      (node (ref "IC37") (pin "Y7") (pinfunction "D03_0_Y7") (pintype "bidirectional"))
      (node (ref "R218") (pin "1") (pinfunction "1_1") (pintype "passive"))
    )
    (net (code "46") (name "/QSPI1_CS_B") (class "Default")
      (node (ref "IC3") (pin "7") (pinfunction "~{S}_7") (pintype "input"))
      (node (ref "R222") (pin "1") (pinfunction "1_1") (pintype "passive"))
    )
    (net (code "47") (name "/QSPI1_IO0") (class "Default")
      (node (ref "IC3") (pin "15") (pinfunction "DQ0_15") (pintype "bidirectional"))
    )
    (net (code "48") (name "/QSPI1_IO1") (class "Default")
      (node (ref "IC3") (pin "8") (pinfunction "DQ1_8") (pintype "bidirectional"))
    )
    (net (code "49") (name "/QSPI1_IO2") (class "Default")
      (node (ref "IC3") (pin "9") (pinfunction "~{W}/DQ2_9") (pintype "bidirectional"))
      (node (ref "R234") (pin "1") (pinfunction "1_1") (pintype "passive"))
    )
    (net (code "50") (name "/QSPI1_IO3") (class "Default")
      (node (ref "IC3") (pin "1") (pinfunction "~{HOLD}/DQ3_1") (pintype "bidirectional"))
      (node (ref "R221") (pin "1") (pinfunction "1_1") (pintype "passive"))
    )
    (net (code "51") (name "/RTM_FPGA_CCLK") (class "Default")
      (node (ref "R223") (pin "2") (pinfunction "2_2") (pintype "passive"))
    )
    (net (code "52") (name "/RTM_FPGA_DIN") (class "Default")
      (node (ref "R224") (pin "2") (pinfunction "2_2") (pintype "passive"))
    )
    (net (code "53") (name "/RTM_FPGA_DONE") (class "Default")
      (node (ref "R225") (pin "2") (pinfunction "2_2") (pintype "passive"))
    )
    (net (code "54") (name "/RTM_FPGA_INIT_B") (class "Default")
      (node (ref "R226") (pin "2") (pinfunction "2_2") (pintype "passive"))
    )
    (net (code "55") (name "/RTM_FPGA_PROGRAM_B") (class "Default")
      (node (ref "R227") (pin "2") (pinfunction "2_2") (pintype "passive"))
    )
    (net (code "56") (name "/SYSMON_VN_R") (class "Default")
      (node (ref "C220") (pin "1") (pinfunction "1_1") (pintype "passive"))
      (node (ref "IC37") (pin "W11") (pinfunction "VN_W11") (pintype "input"))
    )
    (net (code "57") (name "/SYSMON_VP_R") (class "Default")
      (node (ref "C220") (pin "2") (pinfunction "2_2") (pintype "passive"))
      (node (ref "IC37") (pin "V12") (pinfunction "VP_V12") (pintype "input"))
    )
    (net (code "58") (name "/Vref64") (class "Default")
      (node (ref "C219") (pin "1") (pinfunction "1_1") (pintype "passive"))
      (node (ref "IC37") (pin "AD13") (pinfunction "VREF_64_AD13") (pintype "power_in"))
    )
    (net (code "59") (name "/Vref65") (class "Default")
      (node (ref "C218") (pin "1") (pinfunction "1_1") (pintype "passive"))
      (node (ref "IC37") (pin "J21") (pinfunction "VREF_65_J21") (pintype "power_in"))
    )
    (net (code "60") (name "/Vrefp") (class "Default")
      (node (ref "IC37") (pin "W12") (pinfunction "VREFP_W12") (pintype "power_in"))
      (node (ref "R252") (pin "1") (pinfunction "1_1") (pintype "passive"))
    )
    (net (code "67") (name "GND") (class "Default")
      (node (ref "C209") (pin "1") (pinfunction "1_1") (pintype "passive"))
      (node (ref "C210") (pin "2") (pinfunction "2_2") (pintype "passive"))
      (node (ref "C211") (pin "2") (pinfunction "2_2") (pintype "passive"))
      (node (ref "C212") (pin "2") (pinfunction "2_2") (pintype "passive"))
      (node (ref "C213") (pin "2") (pinfunction "2_2") (pintype "passive"))
      (node (ref "C214") (pin "1") (pinfunction "1_1") (pintype "passive"))
      (node (ref "C215") (pin "2") (pinfunction "2_2") (pintype "passive"))
      (node (ref "C216") (pin "1") (pinfunction "1_1") (pintype "passive"))
      (node (ref "C217") (pin "2") (pinfunction "2_2") (pintype "passive"))
      (node (ref "C218") (pin "2") (pinfunction "2_2") (pintype "passive"))
      (node (ref "C219") (pin "2") (pinfunction "2_2") (pintype "passive"))
      (node (ref "C259") (pin "2") (pinfunction "2_2") (pintype "passive"))
      (node (ref "C260") (pin "2") (pinfunction "2_2") (pintype "passive"))
      (node (ref "C511") (pin "1") (pinfunction "1_1") (pintype "passive"))
      (node (ref "IC3") (pin "10") (pinfunction "VSS_10") (pintype "power_in"))
      (node (ref "IC31") (pin "10") (pinfunction "VSS_10") (pintype "power_in"))
      (node (ref "IC35") (pin "7") (pinfunction "GND_7") (pintype "power_in"))
      (node (ref "IC37") (pin "V11") (pinfunction "VREFN_V11") (pintype "power_in"))
      (node (ref "R232") (pin "1") (pinfunction "1_1") (pintype "passive"))
      (node (ref "R235") (pin "1") (pinfunction "1_1") (pintype "passive"))
      (node (ref "R237") (pin "1") (pinfunction "1_1") (pintype "passive"))
      (node (ref "R238") (pin "1") (pinfunction "1_1") (pintype "passive"))
      (node (ref "R241") (pin "1") (pinfunction "1_1") (pintype "passive"))
      (node (ref "R250") (pin "1") (pinfunction "1_1") (pintype "passive"))
      (node (ref "R252") (pin "2") (pinfunction "2_2") (pintype "passive"))
      (node (ref "R576") (pin "1") (pinfunction "1_1") (pintype "passive"))
      (node (ref "T17") (pin "2") (pinfunction "S_2") (pintype "passive"))
    )
    (net (code "68") (name "MGTAVTT") (class "Default")
      (node (ref "IC37") (pin "AP6") (pinfunction "MGTAVTTRCAL_R_AP6") (pintype "input"))
      (node (ref "R527") (pin "2") (pinfunction "2_2") (pintype "passive"))
    )
    (net (code "69") (name "Net-(C511-Pad2)") (class "Default")
      (node (ref "C511") (pin "2") (pinfunction "2_2") (pintype "passive"))
      (node (ref "R253") (pin "1") (pinfunction "1_1") (pintype "passive"))
    )
    (net (code "70") (name "Net-(IC3-~{RESET})") (class "Default")
      (node (ref "IC3") (pin "3") (pinfunction "~{RESET}_3") (pintype "input"))
      (node (ref "R335") (pin "1") (pinfunction "1_1") (pintype "passive"))
    )
    (net (code "71") (name "Net-(IC31-~{RESET})") (class "Default")
      (node (ref "IC31") (pin "3") (pinfunction "~{RESET}_3") (pintype "input"))
      (node (ref "R204") (pin "1") (pinfunction "1_1") (pintype "passive"))
    )
    (net (code "72") (name "Net-(LD17-C)") (class "Default")
      (node (ref "LD17") (pin "1") (pinfunction "C_1") (pintype "passive"))
      (node (ref "R245") (pin "1") (pinfunction "1_1") (pintype "passive"))
    )
    (net (code "73") (name "Net-(R235-Pad2)") (class "Default")
      (node (ref "R235") (pin "2") (pinfunction "2_2") (pintype "passive"))
      (node (ref "SW1") (pin "6") (pinfunction "6_6") (pintype "bidirectional"))
    )
    (net (code "74") (name "Net-(R237-Pad2)") (class "Default")
      (node (ref "R237") (pin "2") (pinfunction "2_2") (pintype "passive"))
      (node (ref "SW1") (pin "7") (pinfunction "7_7") (pintype "bidirectional"))
    )
    (net (code "75") (name "Net-(R238-Pad2)") (class "Default")
      (node (ref "R238") (pin "2") (pinfunction "2_2") (pintype "passive"))
      (node (ref "SW1") (pin "8") (pinfunction "8_8") (pintype "bidirectional"))
    )
    (net (code "76") (name "Net-(R250-Pad2)") (class "Default")
      (node (ref "R250") (pin "2") (pinfunction "2_2") (pintype "passive"))
      (node (ref "SW1") (pin "5") (pinfunction "5_5") (pintype "bidirectional"))
    )
    (net (code "77") (name "Net-(T17-D)") (class "Default")
      (node (ref "R245") (pin "2") (pinfunction "2_2") (pintype "passive"))
      (node (ref "T17") (pin "3") (pinfunction "D_3") (pintype "passive"))
    )
    (net (code "78") (name "P1V8") (class "Default")
      (node (ref "R575") (pin "1") (pinfunction "1_1") (pintype "passive"))
    )
    (net (code "79") (name "P3V3") (class "Default")
      (node (ref "C209") (pin "2") (pinfunction "2_2") (pintype "passive"))
      (node (ref "C214") (pin "2") (pinfunction "2_2") (pintype "passive"))
      (node (ref "IC3") (pin "2") (pinfunction "VCC_2") (pintype "power_in"))
      (node (ref "IC31") (pin "2") (pinfunction "VCC_2") (pintype "power_in"))
      (node (ref "IC37") (pin "W7") (pinfunction "CFGBVS_0_W7") (pintype "input"))
      (node (ref "LD17") (pin "2") (pinfunction "A_2") (pintype "passive"))
      (node (ref "R204") (pin "2") (pinfunction "2_2") (pintype "passive"))
      (node (ref "R218") (pin "2") (pinfunction "2_2") (pintype "passive"))
      (node (ref "R219") (pin "2") (pinfunction "2_2") (pintype "passive"))
      (node (ref "R220") (pin "2") (pinfunction "2_2") (pintype "passive"))
      (node (ref "R221") (pin "2") (pinfunction "2_2") (pintype "passive"))
      (node (ref "R222") (pin "2") (pinfunction "2_2") (pintype "passive"))
      (node (ref "R228") (pin "2") (pinfunction "2_2") (pintype "passive"))
      (node (ref "R229") (pin "2") (pinfunction "2_2") (pintype "passive"))
      (node (ref "R233") (pin "2") (pinfunction "2_2") (pintype "passive"))
      (node (ref "R234") (pin "2") (pinfunction "2_2") (pintype "passive"))
      (node (ref "R236") (pin "1") (pinfunction "1_1") (pintype "passive"))
      (node (ref "R239") (pin "1") (pinfunction "1_1") (pintype "passive"))
      (node (ref "R240") (pin "1") (pinfunction "1_1") (pintype "passive"))
      (node (ref "R249") (pin "1") (pinfunction "1_1") (pintype "passive"))
      (node (ref "R335") (pin "2") (pinfunction "2_2") (pintype "passive"))
    )
    (net (code "80") (name "P3V3MP") (class "Default")
      (node (ref "C216") (pin "2") (pinfunction "2_2") (pintype "passive"))
      (node (ref "IC35") (pin "14") (pinfunction "VCC_14") (pintype "power_in"))
    )
    (net (code "81") (name "unconnected-(HS1-MOUNT1-Pad1)") (class "Default")
      (node (ref "HS1") (pin "1") (pinfunction "MOUNT1_1") (pintype "passive"))
    )
    (net (code "82") (name "unconnected-(HS1-MOUNT2-Pad2)") (class "Default")
      (node (ref "HS1") (pin "2") (pinfunction "MOUNT2_2") (pintype "passive"))
    )
    (net (code "83") (name "unconnected-(IC3-DNU-Pad4)") (class "Default")
      (node (ref "IC3") (pin "4") (pinfunction "DNU_4") (pintype "passive"))
    )
    (net (code "84") (name "unconnected-(IC3-DNU-Pad5)") (class "Default")
      (node (ref "IC3") (pin "5") (pinfunction "DNU_5") (pintype "passive"))
    )
    (net (code "85") (name "unconnected-(IC3-DNU-Pad6)") (class "Default")
      (node (ref "IC3") (pin "6") (pinfunction "DNU_6") (pintype "passive"))
    )
    (net (code "86") (name "unconnected-(IC3-DNU-Pad11)") (class "Default")
      (node (ref "IC3") (pin "11") (pinfunction "DNU_11") (pintype "passive"))
    )
    (net (code "87") (name "unconnected-(IC3-DNU-Pad12)") (class "Default")
      (node (ref "IC3") (pin "12") (pinfunction "DNU_12") (pintype "passive"))
    )
    (net (code "88") (name "unconnected-(IC3-DNU-Pad13)") (class "Default")
      (node (ref "IC3") (pin "13") (pinfunction "DNU_13") (pintype "passive"))
    )
    (net (code "89") (name "unconnected-(IC3-DNU-Pad14)") (class "Default")
      (node (ref "IC3") (pin "14") (pinfunction "DNU_14") (pintype "passive"))
    )
    (net (code "90") (name "unconnected-(IC31-DNU-Pad4)") (class "Default")
      (node (ref "IC31") (pin "4") (pinfunction "DNU_4") (pintype "passive"))
    )
    (net (code "91") (name "unconnected-(IC31-DNU-Pad5)") (class "Default")
      (node (ref "IC31") (pin "5") (pinfunction "DNU_5") (pintype "passive"))
    )
    (net (code "92") (name "unconnected-(IC31-DNU-Pad6)") (class "Default")
      (node (ref "IC31") (pin "6") (pinfunction "DNU_6") (pintype "passive"))
    )
    (net (code "93") (name "unconnected-(IC31-DNU-Pad11)") (class "Default")
      (node (ref "IC31") (pin "11") (pinfunction "DNU_11") (pintype "passive"))
    )
    (net (code "94") (name "unconnected-(IC31-DNU-Pad12)") (class "Default")
      (node (ref "IC31") (pin "12") (pinfunction "DNU_12") (pintype "passive"))
    )
    (net (code "95") (name "unconnected-(IC31-DNU-Pad13)") (class "Default")
      (node (ref "IC31") (pin "13") (pinfunction "DNU_13") (pintype "passive"))
    )
    (net (code "96") (name "unconnected-(IC31-DNU-Pad14)") (class "Default")
      (node (ref "IC31") (pin "14") (pinfunction "DNU_14") (pintype "passive"))
    )
  )
)
